# 02_4G.net
KiCad netlist of a schematic drawn in Altium Designer
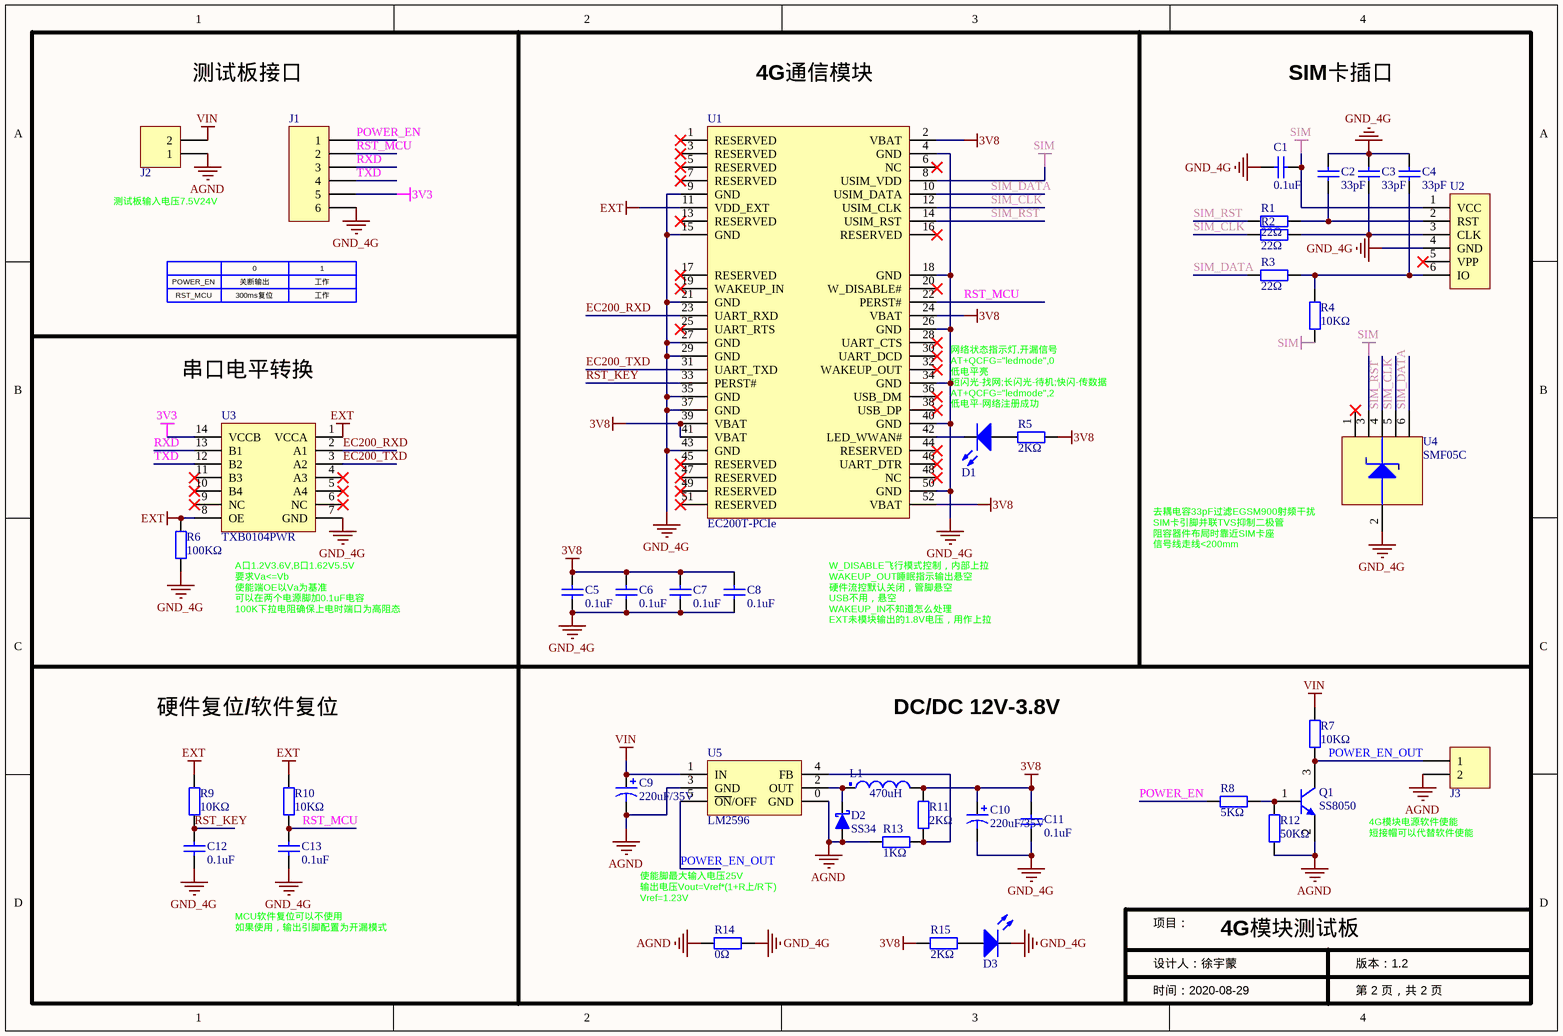
[diagram p0: 02_4G模块测试板原理图.SchDoc]

(export (version "E")
  (design (tool "Eeschema 10.0.6"))
  (components
    (comp (ref "C1")
      (value "0.1uF")
      (footprint "CAP-0603")
      (description "无极性电容")
      (fields (field (name "Comment") "Cap") (field (name "PUBLISHER") "Altium Limited"))
      (libsource (lib "Arrowy_Racing") (part "Cap"))
    )
    (comp (ref "C2")
      (value "33pF")
      (footprint "CAP-0603")
      (description "无极性电容")
      (fields (field (name "Comment") "Cap") (field (name "PUBLISHER") "Altium Limited"))
      (libsource (lib "Arrowy_Racing") (part "Cap"))
    )
    (comp (ref "C3")
      (value "33pF")
      (footprint "CAP-0603")
      (description "无极性电容")
      (fields (field (name "Comment") "Cap") (field (name "PUBLISHER") "Altium Limited"))
      (libsource (lib "Arrowy_Racing") (part "Cap"))
    )
    (comp (ref "C4")
      (value "33pF")
      (footprint "CAP-0603")
      (description "无极性电容")
      (fields (field (name "Comment") "Cap") (field (name "PUBLISHER") "Altium Limited"))
      (libsource (lib "Arrowy_Racing") (part "Cap"))
    )
    (comp (ref "C5")
      (value "0.1uF")
      (footprint "CAP-0603")
      (description "无极性电容")
      (fields (field (name "Comment") "Cap") (field (name "PUBLISHER") "Altium Limited"))
      (libsource (lib "Arrowy_Racing") (part "Cap"))
    )
    (comp (ref "C6")
      (value "0.1uF")
      (footprint "CAP-0603")
      (description "无极性电容")
      (fields (field (name "Comment") "Cap") (field (name "PUBLISHER") "Altium Limited"))
      (libsource (lib "Arrowy_Racing") (part "Cap"))
    )
    (comp (ref "C7")
      (value "0.1uF")
      (footprint "CAP-0603")
      (description "无极性电容")
      (fields (field (name "Comment") "Cap") (field (name "PUBLISHER") "Altium Limited"))
      (libsource (lib "Arrowy_Racing") (part "Cap"))
    )
    (comp (ref "C8")
      (value "0.1uF")
      (footprint "CAP-0603")
      (description "无极性电容")
      (fields (field (name "Comment") "Cap") (field (name "PUBLISHER") "Altium Limited"))
      (libsource (lib "Arrowy_Racing") (part "Cap"))
    )
    (comp (ref "C9")
      (value "220uF/35V")
      (footprint "Cap8x10.5mm")
      (description "贴片电解电容 8*10.5mm")
      (fields (field (name "Comment") "Cap Pol") (field (name "PUBLISHER") "Altium Limited"))
      (libsource (lib "元件库") (part "Cap Pol"))
    )
    (comp (ref "C10")
      (value "220uF/35V")
      (footprint "Cap8x10.5mm")
      (description "贴片电解电容 8*10.5mm")
      (fields (field (name "Comment") "Cap Pol") (field (name "PUBLISHER") "Altium Limited"))
      (libsource (lib "元件库") (part "Cap Pol"))
    )
    (comp (ref "C11")
      (value "0.1uF")
      (footprint "CAP-0603")
      (description "无极性电容")
      (fields (field (name "Comment") "Cap") (field (name "PUBLISHER") "Altium Limited"))
      (libsource (lib "Arrowy_Racing") (part "Cap"))
    )
    (comp (ref "C12")
      (value "0.1uF")
      (footprint "CAP-0603")
      (description "无极性电容")
      (fields (field (name "Comment") "Cap") (field (name "PUBLISHER") "Altium Limited"))
      (libsource (lib "Arrowy_Racing") (part "Cap"))
    )
    (comp (ref "C13")
      (value "0.1uF")
      (footprint "CAP-0603")
      (description "无极性电容")
      (fields (field (name "Comment") "Cap") (field (name "PUBLISHER") "Altium Limited"))
      (libsource (lib "Arrowy_Racing") (part "Cap"))
    )
    (comp (ref "D1")
      (value "LED")
      (footprint "LED_0805")
      (description "发光二极管")
      (fields (field (name "PUBLISHER") "Altium Limited"))
      (libsource (lib "Arrowy_Racing") (part "LED"))
    )
    (comp (ref "D2")
      (value "SS34")
      (footprint "SMA(DO-214AC)")
      (description "Schottky Diode")
      (fields (field (name "PUBLISHER") "Altium Limited"))
      (libsource (lib "元件库") (part "D Schottky"))
    )
    (comp (ref "D3")
      (value "LED")
      (footprint "LED_0805")
      (description "发光二极管")
      (fields (field (name "PUBLISHER") "Altium Limited"))
      (libsource (lib "Arrowy_Racing") (part "LED"))
    )
    (comp (ref "J1")
      (value "Header6")
      (footprint "Header_6x1_2.54_排针")
      (description "接插件")
      (libsource (lib "Arrowy_Racing") (part "Header6"))
    )
    (comp (ref "J2")
      (value "Header 2")
      (footprint "Header_HT_2P_5.08_Right")
      (description "接插件")
      (fields (field (name "PUBLISHER") "Altium Limited"))
      (libsource (lib "Arrowy_Racing") (part "Header 2"))
    )
    (comp (ref "J3")
      (value "Header 2")
      (footprint "Header_2X1_2.54")
      (description "接插件")
      (fields (field (name "PUBLISHER") "Altium Limited"))
      (libsource (lib "") (part "Header 2_1"))
    )
    (comp (ref "L1")
      (value "470uH")
      (footprint "CD43")
      (description "贴片功率电感")
      (fields (field (name "Comment") "Inductor") (field (name "PUBLISHER") "Altium Limited"))
      (libsource (lib "元件库") (part "Inductor"))
    )
    (comp (ref "Q1")
      (value "SS8050")
      (footprint "SOT-23")
      (description "NPN贴片三极管")
      (fields (field (name "PUBLISHER") "Altium Limited"))
      (libsource (lib "Arrowy_Racing") (part "SS8050"))
    )
    (comp (ref "R1")
      (value "22Ω")
      (footprint "0603")
      (description "贴片电阻")
      (fields (field (name "Comment") "Res") (field (name "PUBLISHER") "Altium Limited"))
      (libsource (lib "") (part "Res_1"))
    )
    (comp (ref "R2")
      (value "22Ω")
      (footprint "0603")
      (description "贴片电阻")
      (fields (field (name "Comment") "Res") (field (name "PUBLISHER") "Altium Limited"))
      (libsource (lib "") (part "Res_1"))
    )
    (comp (ref "R3")
      (value "22Ω")
      (footprint "0603")
      (description "贴片电阻")
      (fields (field (name "Comment") "Res") (field (name "PUBLISHER") "Altium Limited"))
      (libsource (lib "") (part "Res_1"))
    )
    (comp (ref "R4")
      (value "10KΩ")
      (footprint "0603")
      (description "贴片电阻")
      (fields (field (name "Comment") "Res") (field (name "PUBLISHER") "Altium Limited"))
      (libsource (lib "Arrowy_Racing") (part "Res"))
    )
    (comp (ref "R5")
      (value "2KΩ")
      (footprint "0603")
      (description "贴片电阻")
      (fields (field (name "Comment") "Res") (field (name "PUBLISHER") "Altium Limited"))
      (libsource (lib "") (part "Res_3"))
    )
    (comp (ref "R6")
      (value "100KΩ")
      (footprint "0603")
      (description "贴片电阻")
      (fields (field (name "Comment") "Res") (field (name "PUBLISHER") "Altium Limited"))
      (libsource (lib "") (part "Res_1"))
    )
    (comp (ref "R7")
      (value "10KΩ")
      (footprint "0603")
      (description "贴片电阻")
      (fields (field (name "Comment") "Res") (field (name "PUBLISHER") "Altium Limited"))
      (libsource (lib "Arrowy_Racing") (part "Res"))
    )
    (comp (ref "R8")
      (value "5KΩ")
      (footprint "0603")
      (description "贴片电阻")
      (fields (field (name "Comment") "Res") (field (name "PUBLISHER") "Altium Limited"))
      (libsource (lib "") (part "Res_1"))
    )
    (comp (ref "R9")
      (value "10KΩ")
      (footprint "0603")
      (description "贴片电阻")
      (fields (field (name "Comment") "Res") (field (name "PUBLISHER") "Altium Limited"))
      (libsource (lib "") (part "Res_2"))
    )
    (comp (ref "R10")
      (value "10KΩ")
      (footprint "0603")
      (description "贴片电阻")
      (fields (field (name "Comment") "Res") (field (name "PUBLISHER") "Altium Limited"))
      (libsource (lib "Arrowy_Racing") (part "Res"))
    )
    (comp (ref "R11")
      (value "2KΩ")
      (footprint "0603")
      (description "贴片电阻")
      (fields (field (name "Comment") "Res") (field (name "PUBLISHER") "Altium Limited"))
      (libsource (lib "Arrowy_Racing") (part "Res"))
    )
    (comp (ref "R12")
      (value "50KΩ")
      (footprint "0603")
      (description "贴片电阻")
      (fields (field (name "Comment") "Res") (field (name "PUBLISHER") "Altium Limited"))
      (libsource (lib "Arrowy_Racing") (part "Res"))
    )
    (comp (ref "R13")
      (value "1KΩ")
      (footprint "0603")
      (description "贴片电阻")
      (fields (field (name "Comment") "Res") (field (name "PUBLISHER") "Altium Limited"))
      (libsource (lib "") (part "Res_1"))
    )
    (comp (ref "R14")
      (value "0Ω")
      (footprint "0805")
      (description "贴片电阻")
      (fields (field (name "Comment") "Res") (field (name "PUBLISHER") "Altium Limited"))
      (libsource (lib "") (part "Res_1"))
    )
    (comp (ref "R15")
      (value "2KΩ")
      (footprint "0603")
      (description "贴片电阻")
      (fields (field (name "Comment") "Res") (field (name "PUBLISHER") "Altium Limited"))
      (libsource (lib "") (part "Res_3"))
    )
    (comp (ref "U1")
      (value "EC200T-PCIe")
      (footprint "miniPCIe1")
      (libsource (lib "Arrowy_Racing") (part "EC200T-PCIe"))
    )
    (comp (ref "U2")
      (value "nano_sim")
      (footprint "Nano_SIM_6P")
      (libsource (lib "Arrowy_Racing") (part "nano_sim"))
    )
    (comp (ref "U3")
      (value "TXB0104PWR")
      (footprint "TSSOP-14")
      (description "电平转换芯片")
      (libsource (lib "Arrowy_Racing") (part "TXB0104PWR"))
    )
    (comp (ref "U4") (value "SMF05C") (footprint "SOT-363") (libsource (lib "Arrowy_Racing") (part "SMF05C")))
    (comp (ref "U5")
      (value "LM2596")
      (footprint "TO-263-5 无背面散热")
      (description "DC/DC")
      (libsource (lib "Arrowy_Racing") (part "LM2596"))
    )
  )
  (nets
    (net (code "1") (name "/EC200_RXD") (class "Default")
      (node (ref "U1") (pin "23") (pinfunction "UART_RXD_23") (pintype "passive"))
      (node (ref "U3") (pin "2") (pinfunction "A1_2") (pintype "passive"))
    )
    (net (code "2") (name "/EC200_TXD") (class "Default")
      (node (ref "U1") (pin "31") (pinfunction "UART_TXD_31") (pintype "passive"))
      (node (ref "U3") (pin "3") (pinfunction "A2_3") (pintype "passive"))
    )
    (net (code "3") (name "/POWER_EN") (class "Default")
      (node (ref "J1") (pin "1") (pinfunction "1_1") (pintype "passive"))
      (node (ref "R8") (pin "1") (pinfunction "1_1") (pintype "passive"))
    )
    (net (code "4") (name "/POWER_EN_OUT") (class "Default")
      (node (ref "J3") (pin "1") (pinfunction "1_1") (pintype "passive"))
      (node (ref "Q1") (pin "3") (pinfunction "C_3") (pintype "passive"))
      (node (ref "R7") (pin "2") (pinfunction "2_2") (pintype "passive"))
      (node (ref "U5") (pin "5") (pinfunction "~{ON}/OFF_5") (pintype "passive"))
    )
    (net (code "5") (name "/RST_KEY") (class "Default")
      (node (ref "C12") (pin "2") (pinfunction "2_2") (pintype "passive"))
      (node (ref "R9") (pin "1") (pinfunction "1_1") (pintype "passive"))
      (node (ref "U1") (pin "33") (pinfunction "PERST#_33") (pintype "passive"))
    )
    (net (code "6") (name "/RST_MCU") (class "Default")
      (node (ref "C13") (pin "1") (pinfunction "1_1") (pintype "passive"))
      (node (ref "J1") (pin "2") (pinfunction "2_2") (pintype "passive"))
      (node (ref "R10") (pin "2") (pinfunction "2_2") (pintype "passive"))
      (node (ref "U1") (pin "22") (pinfunction "PERST#_22") (pintype "passive"))
    )
    (net (code "7") (name "/RXD") (class "Default")
      (node (ref "J1") (pin "3") (pinfunction "3_3") (pintype "passive"))
      (node (ref "U3") (pin "13") (pinfunction "B1_13") (pintype "passive"))
    )
    (net (code "8") (name "/SIM_CLK") (class "Default")
      (node (ref "R2") (pin "1") (pinfunction "1_1") (pintype "passive"))
      (node (ref "U1") (pin "12") (pinfunction "USIM_CLK_12") (pintype "passive"))
      (node (ref "U4") (pin "5") (pinfunction "gnd_5") (pintype "passive"))
    )
    (net (code "9") (name "/SIM_DATA") (class "Default")
      (node (ref "R3") (pin "1") (pinfunction "1_1") (pintype "passive"))
      (node (ref "U1") (pin "10") (pinfunction "USIM_DATA_10") (pintype "passive"))
      (node (ref "U4") (pin "6") (pinfunction "gnd_6") (pintype "passive"))
    )
    (net (code "10") (name "/SIM_RST") (class "Default")
      (node (ref "R1") (pin "1") (pinfunction "1_1") (pintype "passive"))
      (node (ref "U1") (pin "14") (pinfunction "USIM_RST_14") (pintype "passive"))
      (node (ref "U4") (pin "4") (pinfunction "gnd_4") (pintype "passive"))
    )
    (net (code "11") (name "/TXD") (class "Default")
      (node (ref "J1") (pin "4") (pinfunction "4_4") (pintype "passive"))
      (node (ref "U3") (pin "12") (pinfunction "B2_12") (pintype "passive"))
    )
    (net (code "12") (name "3V3") (class "Default")
      (node (ref "J1") (pin "5") (pinfunction "5_5") (pintype "passive"))
      (node (ref "U3") (pin "14") (pinfunction "VCCB_14") (pintype "passive"))
    )
    (net (code "13") (name "3V8") (class "Default")
      (node (ref "C10") (pin "1") (pinfunction "1_1") (pintype "passive"))
      (node (ref "C11") (pin "2") (pinfunction "2_2") (pintype "passive"))
      (node (ref "C5") (pin "2") (pinfunction "2_2") (pintype "passive"))
      (node (ref "C6") (pin "2") (pinfunction "2_2") (pintype "passive"))
      (node (ref "C7") (pin "2") (pinfunction "2_2") (pintype "passive"))
      (node (ref "C8") (pin "2") (pinfunction "2_2") (pintype "passive"))
      (node (ref "L1") (pin "2") (pinfunction "2_2") (pintype "passive"))
      (node (ref "R11") (pin "1") (pinfunction "1_1") (pintype "passive"))
      (node (ref "R15") (pin "2") (pinfunction "2_2") (pintype "passive"))
      (node (ref "R5") (pin "1") (pinfunction "1_1") (pintype "passive"))
      (node (ref "U1") (pin "2") (pinfunction "VBAT_2") (pintype "passive"))
      (node (ref "U1") (pin "24") (pinfunction "VBAT_24") (pintype "passive"))
      (node (ref "U1") (pin "39") (pinfunction "VBAT_39") (pintype "passive"))
      (node (ref "U1") (pin "41") (pinfunction "VBAT_41") (pintype "passive"))
      (node (ref "U1") (pin "52") (pinfunction "VBAT_52") (pintype "passive"))
    )
    (net (code "14") (name "AGND") (class "Default")
      (node (ref "C9") (pin "2") (pinfunction "2_2") (pintype "passive"))
      (node (ref "D2") (pin "1") (pinfunction "A_1") (pintype "passive"))
      (node (ref "J2") (pin "1") (pinfunction "1_1") (pintype "passive"))
      (node (ref "J3") (pin "2") (pinfunction "2_2") (pintype "passive"))
      (node (ref "Q1") (pin "2") (pinfunction "E_2") (pintype "passive"))
      (node (ref "R12") (pin "2") (pinfunction "2_2") (pintype "passive"))
      (node (ref "R13") (pin "1") (pinfunction "1_1") (pintype "passive"))
      (node (ref "R14") (pin "1") (pinfunction "1_1") (pintype "passive"))
      (node (ref "U5") (pin "0") (pinfunction "GND_0") (pintype "passive"))
      (node (ref "U5") (pin "3") (pinfunction "GND_3") (pintype "passive"))
    )
    (net (code "15") (name "EXT") (class "Default")
      (node (ref "R10") (pin "1") (pinfunction "1_1") (pintype "passive"))
      (node (ref "R6") (pin "2") (pinfunction "2_2") (pintype "passive"))
      (node (ref "R9") (pin "2") (pinfunction "2_2") (pintype "passive"))
      (node (ref "U1") (pin "11") (pinfunction "VDD_EXT_11") (pintype "passive"))
      (node (ref "U3") (pin "1") (pinfunction "VCCA_1") (pintype "passive"))
      (node (ref "U3") (pin "8") (pinfunction "OE_8") (pintype "passive"))
    )
    (net (code "16") (name "GND_4G") (class "Default")
      (node (ref "C1") (pin "2") (pinfunction "2_2") (pintype "passive"))
      (node (ref "C10") (pin "2") (pinfunction "2_2") (pintype "passive"))
      (node (ref "C11") (pin "1") (pinfunction "1_1") (pintype "passive"))
      (node (ref "C12") (pin "1") (pinfunction "1_1") (pintype "passive"))
      (node (ref "C13") (pin "2") (pinfunction "2_2") (pintype "passive"))
      (node (ref "C2") (pin "1") (pinfunction "1_1") (pintype "passive"))
      (node (ref "C3") (pin "1") (pinfunction "1_1") (pintype "passive"))
      (node (ref "C4") (pin "2") (pinfunction "2_2") (pintype "passive"))
      (node (ref "C5") (pin "1") (pinfunction "1_1") (pintype "passive"))
      (node (ref "C6") (pin "1") (pinfunction "1_1") (pintype "passive"))
      (node (ref "C7") (pin "1") (pinfunction "1_1") (pintype "passive"))
      (node (ref "C8") (pin "1") (pinfunction "1_1") (pintype "passive"))
      (node (ref "D3") (pin "2") (pinfunction "K_2") (pintype "passive"))
      (node (ref "J1") (pin "6") (pinfunction "6_6") (pintype "passive"))
      (node (ref "R14") (pin "2") (pinfunction "2_2") (pintype "passive"))
      (node (ref "R6") (pin "1") (pinfunction "1_1") (pintype "passive"))
      (node (ref "U1") (pin "15") (pinfunction "GND_15") (pintype "passive"))
      (node (ref "U1") (pin "18") (pinfunction "GND_18") (pintype "passive"))
      (node (ref "U1") (pin "21") (pinfunction "GND_21") (pintype "passive"))
      (node (ref "U1") (pin "26") (pinfunction "GND_26") (pintype "passive"))
      (node (ref "U1") (pin "27") (pinfunction "GND_27") (pintype "passive"))
      (node (ref "U1") (pin "29") (pinfunction "GND_29") (pintype "passive"))
      (node (ref "U1") (pin "34") (pinfunction "GND_34") (pintype "passive"))
      (node (ref "U1") (pin "35") (pinfunction "GND_35") (pintype "passive"))
      (node (ref "U1") (pin "37") (pinfunction "GND_37") (pintype "passive"))
      (node (ref "U1") (pin "4") (pinfunction "GND_4") (pintype "passive"))
      (node (ref "U1") (pin "40") (pinfunction "GND_40") (pintype "passive"))
      (node (ref "U1") (pin "43") (pinfunction "GND_43") (pintype "passive"))
      (node (ref "U1") (pin "50") (pinfunction "GND_50") (pintype "passive"))
      (node (ref "U1") (pin "9") (pinfunction "GND_9") (pintype "passive"))
      (node (ref "U2") (pin "4") (pinfunction "GND_4") (pintype "passive"))
      (node (ref "U3") (pin "7") (pinfunction "GND_7") (pintype "passive"))
      (node (ref "U4") (pin "2") (pinfunction "gnd_2") (pintype "passive"))
    )
    (net (code "17") (name "Net-(D1-A)") (class "Default")
      (node (ref "D1") (pin "1") (pinfunction "A_1") (pintype "passive"))
      (node (ref "R5") (pin "2") (pinfunction "2_2") (pintype "passive"))
    )
    (net (code "18") (name "Net-(D1-K)") (class "Default")
      (node (ref "D1") (pin "2") (pinfunction "K_2") (pintype "passive"))
      (node (ref "U1") (pin "42") (pinfunction "LED_WWAN#_42") (pintype "passive"))
    )
    (net (code "19") (name "Net-(D2-K)") (class "Default")
      (node (ref "D2") (pin "2") (pinfunction "K_2") (pintype "passive"))
      (node (ref "L1") (pin "1") (pinfunction "1_1") (pintype "passive"))
      (node (ref "U5") (pin "2") (pinfunction "OUT_2") (pintype "passive"))
    )
    (net (code "20") (name "Net-(D3-A)") (class "Default")
      (node (ref "D3") (pin "1") (pinfunction "A_1") (pintype "passive"))
      (node (ref "R15") (pin "1") (pinfunction "1_1") (pintype "passive"))
    )
    (net (code "21") (name "Net-(Q1-B)") (class "Default")
      (node (ref "Q1") (pin "1") (pinfunction "B_1") (pintype "passive"))
      (node (ref "R12") (pin "1") (pinfunction "1_1") (pintype "passive"))
      (node (ref "R8") (pin "2") (pinfunction "2_2") (pintype "passive"))
    )
    (net (code "22") (name "Net-(U2-CLK)") (class "Default")
      (node (ref "C3") (pin "2") (pinfunction "2_2") (pintype "passive"))
      (node (ref "R2") (pin "2") (pinfunction "2_2") (pintype "passive"))
      (node (ref "U2") (pin "3") (pinfunction "CLK_3") (pintype "passive"))
    )
    (net (code "23") (name "Net-(U2-IO)") (class "Default")
      (node (ref "C4") (pin "1") (pinfunction "1_1") (pintype "passive"))
      (node (ref "R3") (pin "2") (pinfunction "2_2") (pintype "passive"))
      (node (ref "R4") (pin "1") (pinfunction "1_1") (pintype "passive"))
      (node (ref "U2") (pin "6") (pinfunction "IO_6") (pintype "passive"))
    )
    (net (code "24") (name "Net-(U2-RST)") (class "Default")
      (node (ref "C2") (pin "2") (pinfunction "2_2") (pintype "passive"))
      (node (ref "R1") (pin "2") (pinfunction "2_2") (pintype "passive"))
      (node (ref "U2") (pin "2") (pinfunction "RST_2") (pintype "passive"))
    )
    (net (code "25") (name "Net-(U5-FB)") (class "Default")
      (node (ref "R11") (pin "2") (pinfunction "2_2") (pintype "passive"))
      (node (ref "R13") (pin "2") (pinfunction "2_2") (pintype "passive"))
      (node (ref "U5") (pin "4") (pinfunction "FB_4") (pintype "passive"))
    )
    (net (code "26") (name "SIM") (class "Default")
      (node (ref "C1") (pin "1") (pinfunction "1_1") (pintype "passive"))
      (node (ref "R4") (pin "2") (pinfunction "2_2") (pintype "passive"))
      (node (ref "U1") (pin "8") (pinfunction "USIM_VDD_8") (pintype "passive"))
      (node (ref "U2") (pin "1") (pinfunction "VCC_1") (pintype "passive"))
      (node (ref "U4") (pin "3") (pinfunction "gnd_3") (pintype "passive"))
    )
    (net (code "27") (name "VIN") (class "Default")
      (node (ref "C9") (pin "1") (pinfunction "1_1") (pintype "passive"))
      (node (ref "J2") (pin "2") (pinfunction "2_2") (pintype "passive"))
      (node (ref "R7") (pin "1") (pinfunction "1_1") (pintype "passive"))
      (node (ref "U5") (pin "1") (pinfunction "IN_1") (pintype "passive"))
    )
    (net (code "28") (name "unconnected-(U1-NC-Pad6)") (class "Default")
      (node (ref "U1") (pin "6") (pinfunction "NC_6") (pintype "passive+no_connect"))
    )
    (net (code "29") (name "unconnected-(U1-NC-Pad48)") (class "Default")
      (node (ref "U1") (pin "48") (pinfunction "NC_48") (pintype "passive+no_connect"))
    )
    (net (code "30") (name "unconnected-(U1-RESERVED-Pad1)") (class "Default")
      (node (ref "U1") (pin "1") (pinfunction "RESERVED_1") (pintype "passive+no_connect"))
    )
    (net (code "31") (name "unconnected-(U1-RESERVED-Pad3)") (class "Default")
      (node (ref "U1") (pin "3") (pinfunction "RESERVED_3") (pintype "passive+no_connect"))
    )
    (net (code "32") (name "unconnected-(U1-RESERVED-Pad5)") (class "Default")
      (node (ref "U1") (pin "5") (pinfunction "RESERVED_5") (pintype "passive+no_connect"))
    )
    (net (code "33") (name "unconnected-(U1-RESERVED-Pad7)") (class "Default")
      (node (ref "U1") (pin "7") (pinfunction "RESERVED_7") (pintype "passive+no_connect"))
    )
    (net (code "34") (name "unconnected-(U1-RESERVED-Pad13)") (class "Default")
      (node (ref "U1") (pin "13") (pinfunction "RESERVED_13") (pintype "passive+no_connect"))
    )
    (net (code "35") (name "unconnected-(U1-RESERVED-Pad16)") (class "Default")
      (node (ref "U1") (pin "16") (pinfunction "RESERVED_16") (pintype "passive+no_connect"))
    )
    (net (code "36") (name "unconnected-(U1-RESERVED-Pad17)") (class "Default")
      (node (ref "U1") (pin "17") (pinfunction "RESERVED_17") (pintype "passive+no_connect"))
    )
    (net (code "37") (name "unconnected-(U1-RESERVED-Pad44)") (class "Default")
      (node (ref "U1") (pin "44") (pinfunction "RESERVED_44") (pintype "passive+no_connect"))
    )
    (net (code "38") (name "unconnected-(U1-RESERVED-Pad45)") (class "Default")
      (node (ref "U1") (pin "45") (pinfunction "RESERVED_45") (pintype "passive+no_connect"))
    )
    (net (code "39") (name "unconnected-(U1-RESERVED-Pad47)") (class "Default")
      (node (ref "U1") (pin "47") (pinfunction "RESERVED_47") (pintype "passive+no_connect"))
    )
    (net (code "40") (name "unconnected-(U1-RESERVED-Pad49)") (class "Default")
      (node (ref "U1") (pin "49") (pinfunction "RESERVED_49") (pintype "passive+no_connect"))
    )
    (net (code "41") (name "unconnected-(U1-RESERVED-Pad51)") (class "Default")
      (node (ref "U1") (pin "51") (pinfunction "RESERVED_51") (pintype "passive+no_connect"))
    )
    (net (code "42") (name "unconnected-(U1-UART_CTS-Pad28)") (class "Default")
      (node (ref "U1") (pin "28") (pinfunction "UART_CTS_28") (pintype "passive+no_connect"))
    )
    (net (code "43") (name "unconnected-(U1-UART_DCD-Pad30)") (class "Default")
      (node (ref "U1") (pin "30") (pinfunction "UART_DCD_30") (pintype "passive+no_connect"))
    )
    (net (code "44") (name "unconnected-(U1-UART_DTR-Pad46)") (class "Default")
      (node (ref "U1") (pin "46") (pinfunction "UART_DTR_46") (pintype "passive+no_connect"))
    )
    (net (code "45") (name "unconnected-(U1-UART_RTS-Pad25)") (class "Default")
      (node (ref "U1") (pin "25") (pinfunction "UART_RTS_25") (pintype "passive+no_connect"))
    )
    (net (code "46") (name "unconnected-(U1-USB_DM-Pad36)") (class "Default")
      (node (ref "U1") (pin "36") (pinfunction "USB_DM_36") (pintype "passive+no_connect"))
    )
    (net (code "47") (name "unconnected-(U1-USB_DP-Pad38)") (class "Default")
      (node (ref "U1") (pin "38") (pinfunction "USB_DP_38") (pintype "passive+no_connect"))
    )
    (net (code "48") (name "unconnected-(U1-WAKEUP_IN-Pad19)") (class "Default")
      (node (ref "U1") (pin "19") (pinfunction "WAKEUP_IN_19") (pintype "passive+no_connect"))
    )
    (net (code "49") (name "unconnected-(U1-WAKEUP_OUT-Pad32)") (class "Default")
      (node (ref "U1") (pin "32") (pinfunction "WAKEUP_OUT_32") (pintype "passive+no_connect"))
    )
    (net (code "50") (name "unconnected-(U1-W_DISABLE#-Pad20)") (class "Default")
      (node (ref "U1") (pin "20") (pinfunction "W_DISABLE#_20") (pintype "passive+no_connect"))
    )
    (net (code "51") (name "unconnected-(U2-VPP-Pad5)") (class "Default")
      (node (ref "U2") (pin "5") (pinfunction "VPP_5") (pintype "passive+no_connect"))
    )
    (net (code "52") (name "unconnected-(U3-A3-Pad4)") (class "Default")
      (node (ref "U3") (pin "4") (pinfunction "A3_4") (pintype "passive+no_connect"))
    )
    (net (code "53") (name "unconnected-(U3-A4-Pad5)") (class "Default")
      (node (ref "U3") (pin "5") (pinfunction "A4_5") (pintype "passive+no_connect"))
    )
    (net (code "54") (name "unconnected-(U3-B3-Pad11)") (class "Default")
      (node (ref "U3") (pin "11") (pinfunction "B3_11") (pintype "passive+no_connect"))
    )
    (net (code "55") (name "unconnected-(U3-B4-Pad10)") (class "Default")
      (node (ref "U3") (pin "10") (pinfunction "B4_10") (pintype "passive+no_connect"))
    )
    (net (code "56") (name "unconnected-(U3-NC-Pad6)") (class "Default")
      (node (ref "U3") (pin "6") (pinfunction "NC_6") (pintype "passive+no_connect"))
    )
    (net (code "57") (name "unconnected-(U3-NC-Pad9)") (class "Default")
      (node (ref "U3") (pin "9") (pinfunction "NC_9") (pintype "passive+no_connect"))
    )
    (net (code "58") (name "unconnected-(U4-gnd-Pad1)") (class "Default")
      (node (ref "U4") (pin "1") (pinfunction "gnd_1") (pintype "passive+no_connect"))
    )
  )
)
